# CCD-schematic.net
KiCad netlist of a schematic drawn in EAGLE
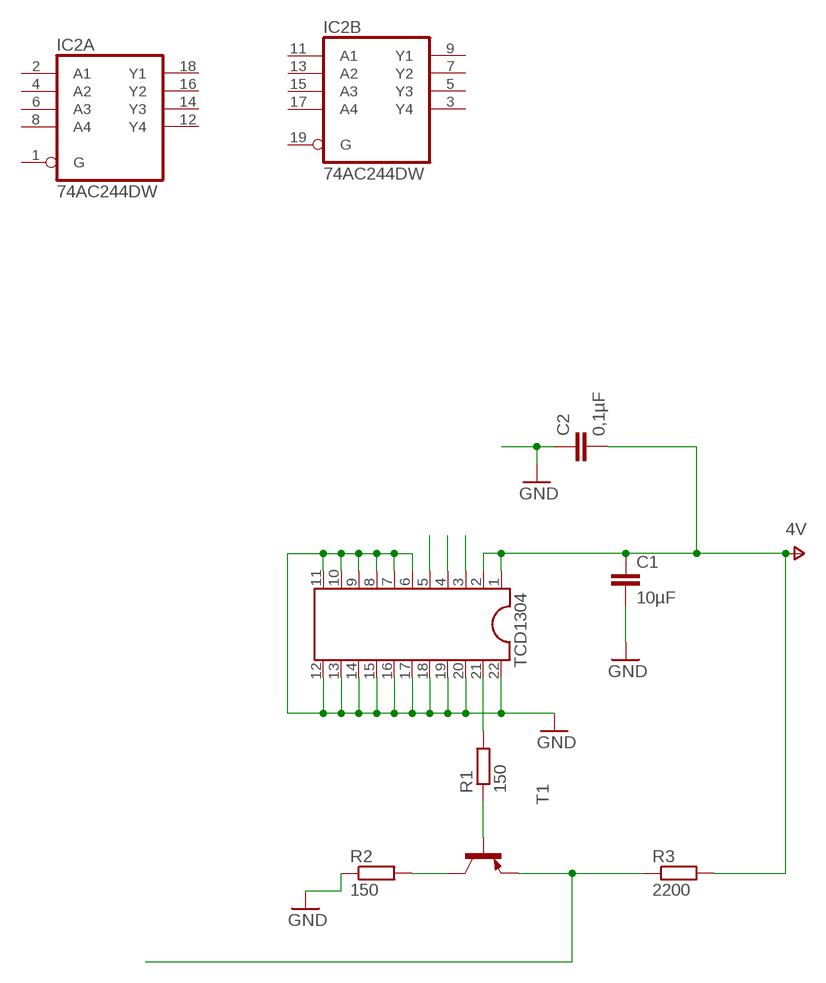
[diagram p0: schematic, sheet 1]

(export (version "E")
  (design (tool "Eeschema 10.0.6"))
  (components
    (comp (ref "C1")
      (value "10µF")
      (footprint "eagle-import:0805")
      (libsource (lib "eagle-import") (part "C0805"))
    )
    (comp (ref "C2")
      (value "0,1µF")
      (footprint "eagle-import:0805")
      (libsource (lib "eagle-import") (part "C0805"))
    )
    (comp (ref "IC2")
      (value "74AC244DW")
      (footprint "eagle-import:SO20W")
      (libsource (lib "eagle-import") (part "74244DWAC"))
    )
    (comp (ref "R1")
      (value "150")
      (footprint "eagle-import:0603")
      (libsource (lib "eagle-import") (part "R0603"))
    )
    (comp (ref "R2")
      (value "150")
      (footprint "eagle-import:0603")
      (libsource (lib "eagle-import") (part "R0603"))
    )
    (comp (ref "R3")
      (value "2200")
      (footprint "eagle-import:0603")
      (libsource (lib "eagle-import") (part "R0603"))
    )
    (comp (ref "T1")
      (value "-PNP-SOT23-EBC")
      (footprint "eagle-import:SOT23-EBC")
      (libsource (lib "eagle-import") (part "-PNP-SOT23-EBC"))
    )
    (comp (ref "TCD1304")
      (value "DIL22-4")
      (footprint "eagle-import:DIL22-4")
      (libsource (lib "eagle-import") (part "DIL22-4"))
    )
  )
  (nets
    (net (code "1") (name "4V") (class "Default")
      (node (ref "C1") (pin "1") (pinfunction "1_1") (pintype "passive"))
      (node (ref "C2") (pin "2") (pinfunction "2_2") (pintype "passive"))
      (node (ref "R3") (pin "2") (pinfunction "2_2") (pintype "passive"))
      (node (ref "TCD1304") (pin "1") (pinfunction "1_1") (pintype "passive"))
      (node (ref "TCD1304") (pin "2") (pinfunction "2_2") (pintype "passive"))
    )
    (net (code "2") (name "GND") (class "Default")
      (node (ref "C1") (pin "2") (pinfunction "2_2") (pintype "passive"))
      (node (ref "C2") (pin "1") (pinfunction "1_1") (pintype "passive"))
      (node (ref "R2") (pin "1") (pinfunction "1_1") (pintype "passive"))
      (node (ref "TCD1304") (pin "10") (pinfunction "10_10") (pintype "passive"))
      (node (ref "TCD1304") (pin "11") (pinfunction "11_11") (pintype "passive"))
      (node (ref "TCD1304") (pin "12") (pinfunction "12_12") (pintype "passive"))
      (node (ref "TCD1304") (pin "13") (pinfunction "13_13") (pintype "passive"))
      (node (ref "TCD1304") (pin "14") (pinfunction "14_14") (pintype "passive"))
      (node (ref "TCD1304") (pin "15") (pinfunction "15_15") (pintype "passive"))
      (node (ref "TCD1304") (pin "16") (pinfunction "16_16") (pintype "passive"))
      (node (ref "TCD1304") (pin "17") (pinfunction "17_17") (pintype "passive"))
      (node (ref "TCD1304") (pin "18") (pinfunction "18_18") (pintype "passive"))
      (node (ref "TCD1304") (pin "19") (pinfunction "19_19") (pintype "passive"))
      (node (ref "TCD1304") (pin "20") (pinfunction "20_20") (pintype "passive"))
      (node (ref "TCD1304") (pin "22") (pinfunction "22_22") (pintype "passive"))
      (node (ref "TCD1304") (pin "6") (pinfunction "6_6") (pintype "passive"))
      (node (ref "TCD1304") (pin "7") (pinfunction "7_7") (pintype "passive"))
      (node (ref "TCD1304") (pin "8") (pinfunction "8_8") (pintype "passive"))
      (node (ref "TCD1304") (pin "9") (pinfunction "9_9") (pintype "passive"))
    )
    (net (code "3") (name "Net-(R1-Pad1)") (class "Default")
      (node (ref "R1") (pin "1") (pinfunction "1_1") (pintype "passive"))
      (node (ref "T1") (pin "B") (pinfunction "B_B") (pintype "passive"))
    )
    (net (code "4") (name "Net-(R1-Pad2)") (class "Default")
      (node (ref "R1") (pin "2") (pinfunction "2_2") (pintype "passive"))
      (node (ref "TCD1304") (pin "21") (pinfunction "21_21") (pintype "passive"))
    )
    (net (code "5") (name "Net-(R2-Pad2)") (class "Default")
      (node (ref "R2") (pin "2") (pinfunction "2_2") (pintype "passive"))
      (node (ref "T1") (pin "C") (pinfunction "C_C") (pintype "passive"))
    )
    (net (code "6") (name "Net-(R3-Pad1)") (class "Default")
      (node (ref "R3") (pin "1") (pinfunction "1_1") (pintype "passive"))
      (node (ref "T1") (pin "E") (pinfunction "E_E") (pintype "passive"))
    )
    (net (code "7") (name "unconnected-(IC2A-A1-Pad2)") (class "Default")
      (node (ref "IC2") (pin "2") (pinfunction "A1_2") (pintype "input"))
    )
    (net (code "8") (name "unconnected-(IC2A-A2-Pad4)") (class "Default")
      (node (ref "IC2") (pin "4") (pinfunction "A2_4") (pintype "input"))
    )
    (net (code "9") (name "unconnected-(IC2A-A3-Pad6)") (class "Default")
      (node (ref "IC2") (pin "6") (pinfunction "A3_6") (pintype "input"))
    )
    (net (code "10") (name "unconnected-(IC2A-A4-Pad8)") (class "Default")
      (node (ref "IC2") (pin "8") (pinfunction "A4_8") (pintype "input"))
    )
    (net (code "11") (name "unconnected-(IC2A-G-Pad1)") (class "Default")
      (node (ref "IC2") (pin "1") (pinfunction "G_1") (pintype "input"))
    )
    (net (code "12") (name "unconnected-(IC2A-Y1-Pad18)") (class "Default")
      (node (ref "IC2") (pin "18") (pinfunction "Y1_18") (pintype "tri_state"))
    )
    (net (code "13") (name "unconnected-(IC2A-Y2-Pad16)") (class "Default")
      (node (ref "IC2") (pin "16") (pinfunction "Y2_16") (pintype "tri_state"))
    )
    (net (code "14") (name "unconnected-(IC2A-Y3-Pad14)") (class "Default")
      (node (ref "IC2") (pin "14") (pinfunction "Y3_14") (pintype "tri_state"))
    )
    (net (code "15") (name "unconnected-(IC2A-Y4-Pad12)") (class "Default")
      (node (ref "IC2") (pin "12") (pinfunction "Y4_12") (pintype "tri_state"))
    )
    (net (code "16") (name "unconnected-(IC2B-A1-Pad11)") (class "Default")
      (node (ref "IC2") (pin "11") (pinfunction "A1_11") (pintype "input"))
    )
    (net (code "17") (name "unconnected-(IC2B-A2-Pad13)") (class "Default")
      (node (ref "IC2") (pin "13") (pinfunction "A2_13") (pintype "input"))
    )
    (net (code "18") (name "unconnected-(IC2B-A3-Pad15)") (class "Default")
      (node (ref "IC2") (pin "15") (pinfunction "A3_15") (pintype "input"))
    )
    (net (code "19") (name "unconnected-(IC2B-A4-Pad17)") (class "Default")
      (node (ref "IC2") (pin "17") (pinfunction "A4_17") (pintype "input"))
    )
    (net (code "20") (name "unconnected-(IC2B-G-Pad19)") (class "Default")
      (node (ref "IC2") (pin "19") (pinfunction "G_19") (pintype "input"))
    )
    (net (code "21") (name "unconnected-(IC2B-Y1-Pad9)") (class "Default")
      (node (ref "IC2") (pin "9") (pinfunction "Y1_9") (pintype "tri_state"))
    )
    (net (code "22") (name "unconnected-(IC2B-Y2-Pad7)") (class "Default")
      (node (ref "IC2") (pin "7") (pinfunction "Y2_7") (pintype "tri_state"))
    )
    (net (code "23") (name "unconnected-(IC2B-Y3-Pad5)") (class "Default")
      (node (ref "IC2") (pin "5") (pinfunction "Y3_5") (pintype "tri_state"))
    )
    (net (code "24") (name "unconnected-(IC2B-Y4-Pad3)") (class "Default")
      (node (ref "IC2") (pin "3") (pinfunction "Y4_3") (pintype "tri_state"))
    )
    (net (code "25") (name "unconnected-(TCD1304-Pad3)") (class "Default")
      (node (ref "TCD1304") (pin "3") (pinfunction "3_3") (pintype "passive"))
    )
    (net (code "26") (name "unconnected-(TCD1304-Pad4)") (class "Default")
      (node (ref "TCD1304") (pin "4") (pinfunction "4_4") (pintype "passive"))
    )
    (net (code "27") (name "unconnected-(TCD1304-Pad5)") (class "Default")
      (node (ref "TCD1304") (pin "5") (pinfunction "5_5") (pintype "passive"))
    )
  )
)
